# tarocco.net
KiCad netlist of a schematic drawn in EAGLE
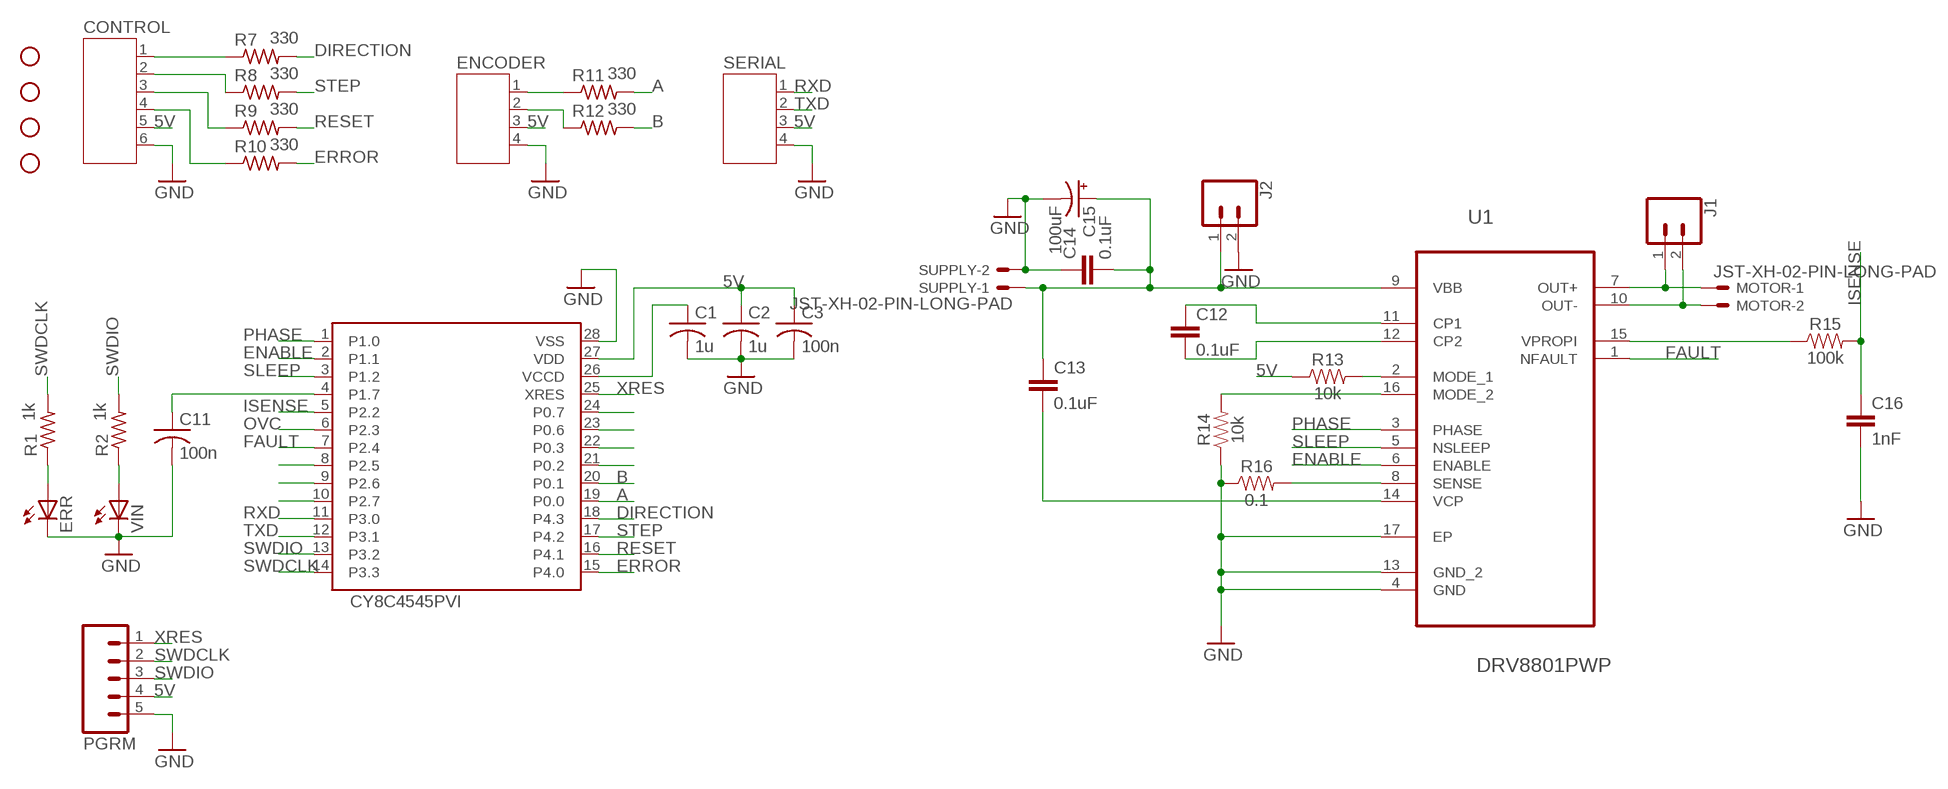
[diagram p0: schematic, sheet 1]

(export (version "E")
  (design (tool "Eeschema 10.0.6"))
  (components
    (comp (ref "C1")
      (value "1u")
      (footprint "eagle-import:C0603")
      (libsource (lib "eagle-import") (part "C-USC0603"))
    )
    (comp (ref "C2")
      (value "1u")
      (footprint "eagle-import:C0603")
      (libsource (lib "eagle-import") (part "C-USC0603"))
    )
    (comp (ref "C3")
      (value "100n")
      (footprint "eagle-import:C0603")
      (libsource (lib "eagle-import") (part "C-USC0603"))
    )
    (comp (ref "C11")
      (value "100n")
      (footprint "eagle-import:C0603")
      (libsource (lib "eagle-import") (part "C-USC0603"))
    )
    (comp (ref "C12")
      (value "0.1uF")
      (footprint "eagle-import:0603")
      (libsource (lib "eagle-import") (part "0.1UF-0603-100V-10%"))
    )
    (comp (ref "C13")
      (value "0.1uF")
      (footprint "eagle-import:0603")
      (libsource (lib "eagle-import") (part "0.1UF-0603-25V-(+80/-20%)"))
    )
    (comp (ref "C14")
      (value "0.1uF")
      (footprint "eagle-import:0603")
      (libsource (lib "eagle-import") (part "0.1UF-0603-25V-(+80/-20%)"))
    )
    (comp (ref "C15")
      (value "100uF")
      (footprint "eagle-import:CPOL-RADIAL-2.5MM-6.5MM")
      (libsource (lib "eagle-import") (part "100UF-POLAR-RADIAL-2.5MM-25V-20%"))
    )
    (comp (ref "C16")
      (value "1nF")
      (footprint "eagle-import:0603")
      (libsource (lib "eagle-import") (part "1.0NF/1000PF-0603-50V-10%"))
    )
    (comp (ref "CONTROL")
      (value "JST-PH6")
      (footprint "eagle-import:JST-PH6")
      (libsource (lib "eagle-import") (part "JST-PH6"))
    )
    (comp (ref "ENCODER")
      (value "JST-PH4")
      (footprint "eagle-import:JST-PH4")
      (libsource (lib "eagle-import") (part "JST-PH4"))
    )
    (comp (ref "ERR")
      (value "LEDCHIP-LED0603")
      (footprint "eagle-import:CHIP-LED0603")
      (libsource (lib "eagle-import") (part "LEDCHIP-LED0603"))
    )
    (comp (ref "IC1")
      (value "CY8C4545PVI")
      (footprint "eagle-import:SSOP28")
      (libsource (lib "eagle-import") (part "CY8C4545PVI"))
    )
    (comp (ref "J1")
      (value "CONN_02PTH3")
      (footprint "eagle-import:1X02_LONGPADS")
      (libsource (lib "eagle-import") (part "CONN_02PTH3"))
    )
    (comp (ref "J2")
      (value "CONN_02PTH3")
      (footprint "eagle-import:1X02_LONGPADS")
      (libsource (lib "eagle-import") (part "CONN_02PTH3"))
    )
    (comp (ref "MOTOR")
      (value "JST-XH-02-PIN-LONG-PAD")
      (footprint "eagle-import:JST-XH-02-PACKAGE-LONG-PAD")
      (libsource (lib "eagle-import") (part "JST-XH-02-PIN-LONG-PAD"))
    )
    (comp (ref "PGRM")
      (value "M05SMD2")
      (footprint "eagle-import:1X05-1MM-RA")
      (libsource (lib "eagle-import") (part "M05SMD2"))
    )
    (comp (ref "R1")
      (value "1k")
      (footprint "eagle-import:R0603")
      (libsource (lib "eagle-import") (part "R-US_R0603"))
    )
    (comp (ref "R2")
      (value "1k")
      (footprint "eagle-import:R0603")
      (libsource (lib "eagle-import") (part "R-US_R0603"))
    )
    (comp (ref "R7")
      (value "330")
      (footprint "eagle-import:R0603")
      (libsource (lib "eagle-import") (part "R-US_R0603"))
    )
    (comp (ref "R8")
      (value "330")
      (footprint "eagle-import:R0603")
      (libsource (lib "eagle-import") (part "R-US_R0603"))
    )
    (comp (ref "R9")
      (value "330")
      (footprint "eagle-import:R0603")
      (libsource (lib "eagle-import") (part "R-US_R0603"))
    )
    (comp (ref "R10")
      (value "330")
      (footprint "eagle-import:R0603")
      (libsource (lib "eagle-import") (part "R-US_R0603"))
    )
    (comp (ref "R11")
      (value "330")
      (footprint "eagle-import:R0603")
      (libsource (lib "eagle-import") (part "R-US_R0603"))
    )
    (comp (ref "R12")
      (value "330")
      (footprint "eagle-import:R0603")
      (libsource (lib "eagle-import") (part "R-US_R0603"))
    )
    (comp (ref "R13")
      (value "10k")
      (footprint "eagle-import:0603")
      (libsource (lib "eagle-import") (part "10KOHM-0603-1/10W-1%"))
    )
    (comp (ref "R14")
      (value "10k")
      (footprint "eagle-import:0603")
      (libsource (lib "eagle-import") (part "10KOHM-0603-1/10W-1%"))
    )
    (comp (ref "R15")
      (value "100k")
      (footprint "eagle-import:0603")
      (libsource (lib "eagle-import") (part "100KOHM-0603-1/10W-1%"))
    )
    (comp (ref "R16")
      (value "0.1")
      (footprint "eagle-import:1210")
      (libsource (lib "eagle-import") (part "0.1OHM-1210-1/2W-1%"))
    )
    (comp (ref "SERIAL")
      (value "JST-PH4")
      (footprint "eagle-import:JST-PH4")
      (libsource (lib "eagle-import") (part "JST-PH4"))
    )
    (comp (ref "STANDOFF1")
      (value "STAND-OFF")
      (footprint "eagle-import:STAND-OFF")
      (libsource (lib "eagle-import") (part "STAND-OFF"))
    )
    (comp (ref "STANDOFF2")
      (value "STAND-OFF")
      (footprint "eagle-import:STAND-OFF")
      (libsource (lib "eagle-import") (part "STAND-OFF"))
    )
    (comp (ref "STANDOFF3")
      (value "STAND-OFF")
      (footprint "eagle-import:STAND-OFF")
      (libsource (lib "eagle-import") (part "STAND-OFF"))
    )
    (comp (ref "STANDOFF4")
      (value "STAND-OFF")
      (footprint "eagle-import:STAND-OFF")
      (libsource (lib "eagle-import") (part "STAND-OFF"))
    )
    (comp (ref "SUPPLY")
      (value "JST-XH-02-PIN-LONG-PAD")
      (footprint "eagle-import:JST-XH-02-PACKAGE-LONG-PAD")
      (libsource (lib "eagle-import") (part "JST-XH-02-PIN-LONG-PAD"))
    )
    (comp (ref "U1")
      (value "DRV8801PWP")
      (footprint "eagle-import:SOP65P640X120-17N")
      (fields (field (name "MF") "Texas Instruments"))
      (libsource (lib "eagle-import") (part "DRV8801PWP"))
    )
    (comp (ref "VIN")
      (value "LEDCHIP-LED0603")
      (footprint "eagle-import:CHIP-LED0603")
      (libsource (lib "eagle-import") (part "LEDCHIP-LED0603"))
    )
  )
  (nets
    (net (code "1") (name "/5V") (class "Default")
      (node (ref "C2") (pin "1") (pinfunction "1_1") (pintype "passive"))
      (node (ref "C3") (pin "1") (pinfunction "1_1") (pintype "passive"))
      (node (ref "CONTROL") (pin "5") (pinfunction "5_5") (pintype "passive"))
      (node (ref "ENCODER") (pin "3") (pinfunction "3_3") (pintype "passive"))
      (node (ref "IC1") (pin "27") (pinfunction "VDD_27") (pintype "power_in"))
      (node (ref "PGRM") (pin "4") (pinfunction "4_4") (pintype "passive"))
      (node (ref "R13") (pin "1") (pinfunction "1_1") (pintype "passive"))
      (node (ref "SERIAL") (pin "3") (pinfunction "3_3") (pintype "passive"))
    )
    (net (code "2") (name "/A") (class "Default")
      (node (ref "IC1") (pin "19") (pinfunction "P0.0_19") (pintype "bidirectional"))
      (node (ref "R11") (pin "2") (pinfunction "2_2") (pintype "passive"))
    )
    (net (code "3") (name "/B") (class "Default")
      (node (ref "IC1") (pin "20") (pinfunction "P0.1_20") (pintype "bidirectional"))
      (node (ref "R12") (pin "2") (pinfunction "2_2") (pintype "passive"))
    )
    (net (code "4") (name "/DIRECTION") (class "Default")
      (node (ref "IC1") (pin "18") (pinfunction "P4.3_18") (pintype "bidirectional"))
      (node (ref "R7") (pin "2") (pinfunction "2_2") (pintype "passive"))
    )
    (net (code "5") (name "/ENABLE") (class "Default")
      (node (ref "IC1") (pin "2") (pinfunction "P1.1_2") (pintype "bidirectional"))
      (node (ref "U1") (pin "6") (pinfunction "ENABLE_6") (pintype "input"))
    )
    (net (code "6") (name "/ERROR") (class "Default")
      (node (ref "IC1") (pin "15") (pinfunction "P4.0_15") (pintype "bidirectional"))
      (node (ref "R10") (pin "2") (pinfunction "2_2") (pintype "passive"))
    )
    (net (code "7") (name "/FAULT") (class "Default")
      (node (ref "IC1") (pin "7") (pinfunction "P2.4_7") (pintype "bidirectional"))
      (node (ref "U1") (pin "1") (pinfunction "NFAULT_1") (pintype "output"))
    )
    (net (code "8") (name "/ISENSE") (class "Default")
      (node (ref "C16") (pin "1") (pinfunction "1_1") (pintype "passive"))
      (node (ref "IC1") (pin "5") (pinfunction "P2.2_5") (pintype "bidirectional"))
      (node (ref "R15") (pin "2") (pinfunction "2_2") (pintype "passive"))
    )
    (net (code "9") (name "/OVC") (class "Default")
      (node (ref "IC1") (pin "6") (pinfunction "P2.3_6") (pintype "bidirectional"))
    )
    (net (code "10") (name "/PHASE") (class "Default")
      (node (ref "IC1") (pin "1") (pinfunction "P1.0_1") (pintype "bidirectional"))
      (node (ref "U1") (pin "3") (pinfunction "PHASE_3") (pintype "input"))
    )
    (net (code "11") (name "/RESET") (class "Default")
      (node (ref "IC1") (pin "16") (pinfunction "P4.1_16") (pintype "bidirectional"))
      (node (ref "R9") (pin "2") (pinfunction "2_2") (pintype "passive"))
    )
    (net (code "12") (name "/RXD") (class "Default")
      (node (ref "IC1") (pin "11") (pinfunction "P3.0_11") (pintype "bidirectional"))
      (node (ref "SERIAL") (pin "1") (pinfunction "1_1") (pintype "passive"))
    )
    (net (code "13") (name "/SLEEP") (class "Default")
      (node (ref "IC1") (pin "3") (pinfunction "P1.2_3") (pintype "bidirectional"))
      (node (ref "U1") (pin "5") (pinfunction "NSLEEP_5") (pintype "input"))
    )
    (net (code "14") (name "/STEP") (class "Default")
      (node (ref "IC1") (pin "17") (pinfunction "P4.2_17") (pintype "bidirectional"))
      (node (ref "R8") (pin "2") (pinfunction "2_2") (pintype "passive"))
    )
    (net (code "15") (name "/SWDCLK") (class "Default")
      (node (ref "IC1") (pin "14") (pinfunction "P3.3_14") (pintype "bidirectional"))
      (node (ref "PGRM") (pin "2") (pinfunction "2_2") (pintype "passive"))
      (node (ref "R1") (pin "2") (pinfunction "2_2") (pintype "passive"))
    )
    (net (code "16") (name "/SWDIO") (class "Default")
      (node (ref "IC1") (pin "13") (pinfunction "P3.2_13") (pintype "bidirectional"))
      (node (ref "PGRM") (pin "3") (pinfunction "3_3") (pintype "passive"))
      (node (ref "R2") (pin "2") (pinfunction "2_2") (pintype "passive"))
    )
    (net (code "17") (name "/TXD") (class "Default")
      (node (ref "IC1") (pin "12") (pinfunction "P3.1_12") (pintype "bidirectional"))
      (node (ref "SERIAL") (pin "2") (pinfunction "2_2") (pintype "passive"))
    )
    (net (code "18") (name "/XRES") (class "Default")
      (node (ref "IC1") (pin "25") (pinfunction "XRES_25") (pintype "bidirectional"))
      (node (ref "PGRM") (pin "1") (pinfunction "1_1") (pintype "passive"))
    )
    (net (code "19") (name "GND") (class "Default")
      (node (ref "C1") (pin "2") (pinfunction "2_2") (pintype "passive"))
      (node (ref "C11") (pin "2") (pinfunction "2_2") (pintype "passive"))
      (node (ref "C14") (pin "1") (pinfunction "1_1") (pintype "passive"))
      (node (ref "C15") (pin "2") (pinfunction "-_2") (pintype "passive"))
      (node (ref "C16") (pin "2") (pinfunction "2_2") (pintype "passive"))
      (node (ref "C2") (pin "2") (pinfunction "2_2") (pintype "passive"))
      (node (ref "C3") (pin "2") (pinfunction "2_2") (pintype "passive"))
      (node (ref "CONTROL") (pin "6") (pinfunction "6_6") (pintype "passive"))
      (node (ref "ENCODER") (pin "4") (pinfunction "4_4") (pintype "passive"))
      (node (ref "ERR") (pin "C") (pinfunction "C_C") (pintype "passive"))
      (node (ref "IC1") (pin "28") (pinfunction "VSS_28") (pintype "power_in"))
      (node (ref "J2") (pin "2") (pinfunction "2_2") (pintype "passive"))
      (node (ref "PGRM") (pin "5") (pinfunction "5_5") (pintype "passive"))
      (node (ref "R14") (pin "1") (pinfunction "1_1") (pintype "passive"))
      (node (ref "R16") (pin "1") (pinfunction "1_1") (pintype "passive"))
      (node (ref "SERIAL") (pin "4") (pinfunction "4_4") (pintype "passive"))
      (node (ref "SUPPLY") (pin "2") (pinfunction "S_2") (pintype "passive"))
      (node (ref "U1") (pin "13") (pinfunction "GND_2_13") (pintype "passive"))
      (node (ref "U1") (pin "17") (pinfunction "EP_17") (pintype "passive"))
      (node (ref "U1") (pin "4") (pinfunction "GND_4") (pintype "passive"))
      (node (ref "VIN") (pin "C") (pinfunction "C_C") (pintype "passive"))
    )
    (net (code "20") (name "Net-(C15-+)") (class "Default")
      (node (ref "C13") (pin "1") (pinfunction "1_1") (pintype "passive"))
      (node (ref "C14") (pin "2") (pinfunction "2_2") (pintype "passive"))
      (node (ref "C15") (pin "1") (pinfunction "+_1") (pintype "passive"))
      (node (ref "J2") (pin "1") (pinfunction "1_1") (pintype "passive"))
      (node (ref "SUPPLY") (pin "1") (pinfunction "S_1") (pintype "passive"))
      (node (ref "U1") (pin "9") (pinfunction "VBB_9") (pintype "power_in"))
    )
    (net (code "21") (name "Net-(CONTROL-Pad1)") (class "Default")
      (node (ref "CONTROL") (pin "1") (pinfunction "1_1") (pintype "passive"))
      (node (ref "R7") (pin "1") (pinfunction "1_1") (pintype "passive"))
    )
    (net (code "22") (name "Net-(CONTROL-Pad2)") (class "Default")
      (node (ref "CONTROL") (pin "2") (pinfunction "2_2") (pintype "passive"))
      (node (ref "R8") (pin "1") (pinfunction "1_1") (pintype "passive"))
    )
    (net (code "23") (name "Net-(CONTROL-Pad3)") (class "Default")
      (node (ref "CONTROL") (pin "3") (pinfunction "3_3") (pintype "passive"))
      (node (ref "R9") (pin "1") (pinfunction "1_1") (pintype "passive"))
    )
    (net (code "24") (name "Net-(CONTROL-Pad4)") (class "Default")
      (node (ref "CONTROL") (pin "4") (pinfunction "4_4") (pintype "passive"))
      (node (ref "R10") (pin "1") (pinfunction "1_1") (pintype "passive"))
    )
    (net (code "25") (name "Net-(ENCODER-Pad1)") (class "Default")
      (node (ref "ENCODER") (pin "1") (pinfunction "1_1") (pintype "passive"))
      (node (ref "R11") (pin "1") (pinfunction "1_1") (pintype "passive"))
    )
    (net (code "26") (name "Net-(ENCODER-Pad2)") (class "Default")
      (node (ref "ENCODER") (pin "2") (pinfunction "2_2") (pintype "passive"))
      (node (ref "R12") (pin "1") (pinfunction "1_1") (pintype "passive"))
    )
    (net (code "27") (name "Net-(ERR-PadA)") (class "Default")
      (node (ref "ERR") (pin "A") (pinfunction "A_A") (pintype "passive"))
      (node (ref "R1") (pin "1") (pinfunction "1_1") (pintype "passive"))
    )
    (net (code "28") (name "Net-(IC1-P1.7)") (class "Default")
      (node (ref "C11") (pin "1") (pinfunction "1_1") (pintype "passive"))
      (node (ref "IC1") (pin "4") (pinfunction "P1.7_4") (pintype "bidirectional"))
    )
    (net (code "29") (name "Net-(IC1-VCCD)") (class "Default")
      (node (ref "C1") (pin "1") (pinfunction "1_1") (pintype "passive"))
      (node (ref "IC1") (pin "26") (pinfunction "VCCD_26") (pintype "power_in"))
    )
    (net (code "30") (name "Net-(MOTORA-S)") (class "Default")
      (node (ref "J1") (pin "1") (pinfunction "1_1") (pintype "passive"))
      (node (ref "MOTOR") (pin "1") (pinfunction "S_1") (pintype "passive"))
      (node (ref "U1") (pin "7") (pinfunction "OUT+_7") (pintype "output"))
    )
    (net (code "31") (name "Net-(MOTORB-S)") (class "Default")
      (node (ref "J1") (pin "2") (pinfunction "2_2") (pintype "passive"))
      (node (ref "MOTOR") (pin "2") (pinfunction "S_2") (pintype "passive"))
      (node (ref "U1") (pin "10") (pinfunction "OUT-_10") (pintype "output"))
    )
    (net (code "32") (name "Net-(R2-Pad1)") (class "Default")
      (node (ref "R2") (pin "1") (pinfunction "1_1") (pintype "passive"))
      (node (ref "VIN") (pin "A") (pinfunction "A_A") (pintype "passive"))
    )
    (net (code "33") (name "Net-(U1-CP1)") (class "Default")
      (node (ref "C12") (pin "1") (pinfunction "1_1") (pintype "passive"))
      (node (ref "U1") (pin "11") (pinfunction "CP1_11") (pintype "input"))
    )
    (net (code "34") (name "Net-(U1-CP2)") (class "Default")
      (node (ref "C12") (pin "2") (pinfunction "2_2") (pintype "passive"))
      (node (ref "U1") (pin "12") (pinfunction "CP2_12") (pintype "input"))
    )
    (net (code "35") (name "Net-(U1-MODE_1)") (class "Default")
      (node (ref "R13") (pin "2") (pinfunction "2_2") (pintype "passive"))
      (node (ref "U1") (pin "2") (pinfunction "MODE_1_2") (pintype "input"))
    )
    (net (code "36") (name "Net-(U1-MODE_2)") (class "Default")
      (node (ref "R14") (pin "2") (pinfunction "2_2") (pintype "passive"))
      (node (ref "U1") (pin "16") (pinfunction "MODE_2_16") (pintype "input"))
    )
    (net (code "37") (name "Net-(U1-SENSE)") (class "Default")
      (node (ref "R16") (pin "2") (pinfunction "2_2") (pintype "passive"))
      (node (ref "U1") (pin "8") (pinfunction "SENSE_8") (pintype "input"))
    )
    (net (code "38") (name "Net-(U1-VCP)") (class "Default")
      (node (ref "C13") (pin "2") (pinfunction "2_2") (pintype "passive"))
      (node (ref "U1") (pin "14") (pinfunction "VCP_14") (pintype "input"))
    )
    (net (code "39") (name "Net-(U1-VPROPI)") (class "Default")
      (node (ref "R15") (pin "1") (pinfunction "1_1") (pintype "passive"))
      (node (ref "U1") (pin "15") (pinfunction "VPROPI_15") (pintype "output"))
    )
    (net (code "40") (name "unconnected-(IC1-P0.2-Pad21)") (class "Default")
      (node (ref "IC1") (pin "21") (pinfunction "P0.2_21") (pintype "bidirectional"))
    )
    (net (code "41") (name "unconnected-(IC1-P0.3-Pad22)") (class "Default")
      (node (ref "IC1") (pin "22") (pinfunction "P0.3_22") (pintype "bidirectional"))
    )
    (net (code "42") (name "unconnected-(IC1-P0.6-Pad23)") (class "Default")
      (node (ref "IC1") (pin "23") (pinfunction "P0.6_23") (pintype "bidirectional"))
    )
    (net (code "43") (name "unconnected-(IC1-P0.7-Pad24)") (class "Default")
      (node (ref "IC1") (pin "24") (pinfunction "P0.7_24") (pintype "bidirectional"))
    )
    (net (code "44") (name "unconnected-(IC1-P2.5-Pad8)") (class "Default")
      (node (ref "IC1") (pin "8") (pinfunction "P2.5_8") (pintype "bidirectional"))
    )
    (net (code "45") (name "unconnected-(IC1-P2.6-Pad9)") (class "Default")
      (node (ref "IC1") (pin "9") (pinfunction "P2.6_9") (pintype "bidirectional"))
    )
    (net (code "46") (name "unconnected-(IC1-P2.7-Pad10)") (class "Default")
      (node (ref "IC1") (pin "10") (pinfunction "P2.7_10") (pintype "bidirectional"))
    )
  )
)
